# cell_fuses.net
KiCad netlist of a schematic drawn in Altium Designer
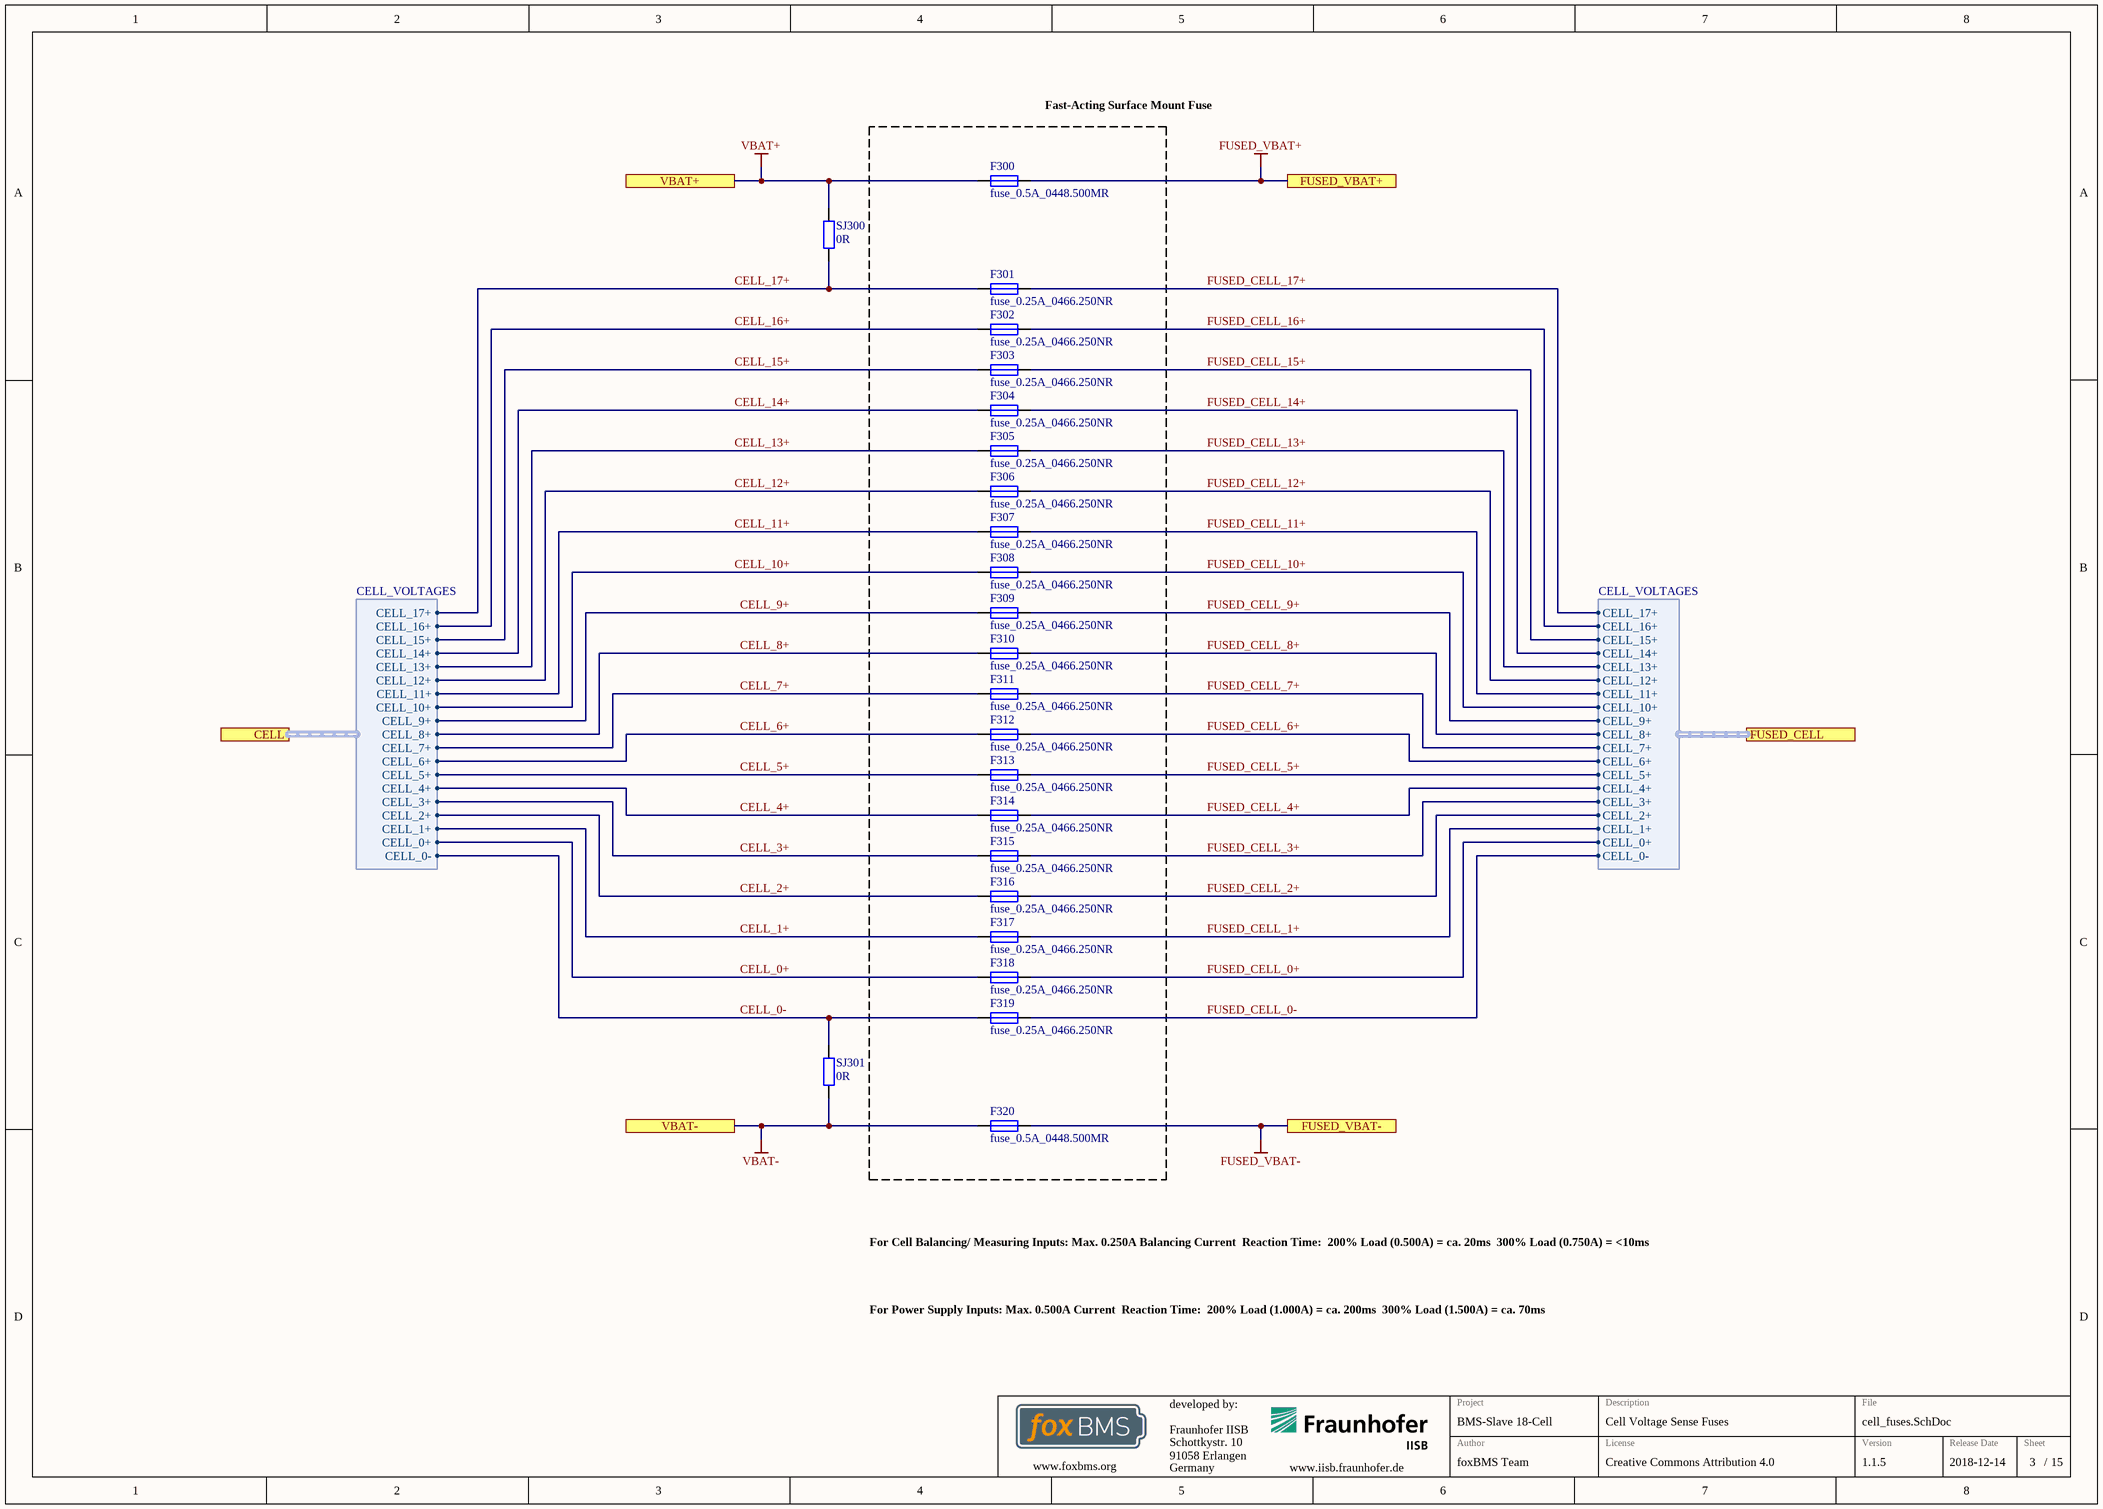
[diagram p0: cell_fuses.SchDoc]

(export (version "E")
  (design (tool "Eeschema 10.0.6"))
  (components
    (comp (ref "F300")
      (value "fuse_0.5A_0448.500MR")
      (footprint "LITTLEFUSE_448")
      (description "Fuse, Surface Mount, NANO2 Series, 500 mA, 125 VAC, 32 VDC, Very Fast Acting, SMD")
      (fields (field (name "MANUFACTURER") "Littlefuse"))
      (libsource (lib "OE750") (part "R_Fuse"))
    )
    (comp (ref "F301")
      (value "fuse_0.25A_0466.250NR")
      (footprint "LITTLEFUSE_466")
      (description "Fuse, Surface Mount, 466 Series, 250 mA, 125 VAC, 125 VDC, Very Fast Acting, 1206")
      (fields (field (name "MANUFACTURER") "Littlefuse"))
      (libsource (lib "OE750") (part "R_Fuse"))
    )
    (comp (ref "F302")
      (value "fuse_0.25A_0466.250NR")
      (footprint "LITTLEFUSE_466")
      (description "Fuse, Surface Mount, 466 Series, 250 mA, 125 VAC, 125 VDC, Very Fast Acting, 1206")
      (fields (field (name "MANUFACTURER") "Littlefuse"))
      (libsource (lib "OE750") (part "R_Fuse"))
    )
    (comp (ref "F303")
      (value "fuse_0.25A_0466.250NR")
      (footprint "LITTLEFUSE_466")
      (description "Fuse, Surface Mount, 466 Series, 250 mA, 125 VAC, 125 VDC, Very Fast Acting, 1206")
      (fields (field (name "MANUFACTURER") "Littlefuse"))
      (libsource (lib "OE750") (part "R_Fuse"))
    )
    (comp (ref "F304")
      (value "fuse_0.25A_0466.250NR")
      (footprint "LITTLEFUSE_466")
      (description "Fuse, Surface Mount, 466 Series, 250 mA, 125 VAC, 125 VDC, Very Fast Acting, 1206")
      (fields (field (name "MANUFACTURER") "Littlefuse"))
      (libsource (lib "OE750") (part "R_Fuse"))
    )
    (comp (ref "F305")
      (value "fuse_0.25A_0466.250NR")
      (footprint "LITTLEFUSE_466")
      (description "Fuse, Surface Mount, 466 Series, 250 mA, 125 VAC, 125 VDC, Very Fast Acting, 1206")
      (fields (field (name "MANUFACTURER") "Littlefuse"))
      (libsource (lib "OE750") (part "R_Fuse"))
    )
    (comp (ref "F306")
      (value "fuse_0.25A_0466.250NR")
      (footprint "LITTLEFUSE_466")
      (description "Fuse, Surface Mount, 466 Series, 250 mA, 125 VAC, 125 VDC, Very Fast Acting, 1206")
      (fields (field (name "MANUFACTURER") "Littlefuse"))
      (libsource (lib "OE750") (part "R_Fuse"))
    )
    (comp (ref "F307")
      (value "fuse_0.25A_0466.250NR")
      (footprint "LITTLEFUSE_466")
      (description "Fuse, Surface Mount, 466 Series, 250 mA, 125 VAC, 125 VDC, Very Fast Acting, 1206")
      (fields (field (name "MANUFACTURER") "Littlefuse"))
      (libsource (lib "OE750") (part "R_Fuse"))
    )
    (comp (ref "F308")
      (value "fuse_0.25A_0466.250NR")
      (footprint "LITTLEFUSE_466")
      (description "Fuse, Surface Mount, 466 Series, 250 mA, 125 VAC, 125 VDC, Very Fast Acting, 1206")
      (fields (field (name "MANUFACTURER") "Littlefuse"))
      (libsource (lib "OE750") (part "R_Fuse"))
    )
    (comp (ref "F309")
      (value "fuse_0.25A_0466.250NR")
      (footprint "LITTLEFUSE_466")
      (description "Fuse, Surface Mount, 466 Series, 250 mA, 125 VAC, 125 VDC, Very Fast Acting, 1206")
      (fields (field (name "MANUFACTURER") "Littlefuse"))
      (libsource (lib "OE750") (part "R_Fuse"))
    )
    (comp (ref "F310")
      (value "fuse_0.25A_0466.250NR")
      (footprint "LITTLEFUSE_466")
      (description "Fuse, Surface Mount, 466 Series, 250 mA, 125 VAC, 125 VDC, Very Fast Acting, 1206")
      (fields (field (name "MANUFACTURER") "Littlefuse"))
      (libsource (lib "OE750") (part "R_Fuse"))
    )
    (comp (ref "F311")
      (value "fuse_0.25A_0466.250NR")
      (footprint "LITTLEFUSE_466")
      (description "Fuse, Surface Mount, 466 Series, 250 mA, 125 VAC, 125 VDC, Very Fast Acting, 1206")
      (fields (field (name "MANUFACTURER") "Littlefuse"))
      (libsource (lib "OE750") (part "R_Fuse"))
    )
    (comp (ref "F312")
      (value "fuse_0.25A_0466.250NR")
      (footprint "LITTLEFUSE_466")
      (description "Fuse, Surface Mount, 466 Series, 250 mA, 125 VAC, 125 VDC, Very Fast Acting, 1206")
      (fields (field (name "MANUFACTURER") "Littlefuse"))
      (libsource (lib "OE750") (part "R_Fuse"))
    )
    (comp (ref "F313")
      (value "fuse_0.25A_0466.250NR")
      (footprint "LITTLEFUSE_466")
      (description "Fuse, Surface Mount, 466 Series, 250 mA, 125 VAC, 125 VDC, Very Fast Acting, 1206")
      (fields (field (name "MANUFACTURER") "Littlefuse"))
      (libsource (lib "OE750") (part "R_Fuse"))
    )
    (comp (ref "F314")
      (value "fuse_0.25A_0466.250NR")
      (footprint "LITTLEFUSE_466")
      (description "Fuse, Surface Mount, 466 Series, 250 mA, 125 VAC, 125 VDC, Very Fast Acting, 1206")
      (fields (field (name "MANUFACTURER") "Littlefuse"))
      (libsource (lib "OE750") (part "R_Fuse"))
    )
    (comp (ref "F315")
      (value "fuse_0.25A_0466.250NR")
      (footprint "LITTLEFUSE_466")
      (description "Fuse, Surface Mount, 466 Series, 250 mA, 125 VAC, 125 VDC, Very Fast Acting, 1206")
      (fields (field (name "MANUFACTURER") "Littlefuse"))
      (libsource (lib "OE750") (part "R_Fuse"))
    )
    (comp (ref "F316")
      (value "fuse_0.25A_0466.250NR")
      (footprint "LITTLEFUSE_466")
      (description "Fuse, Surface Mount, 466 Series, 250 mA, 125 VAC, 125 VDC, Very Fast Acting, 1206")
      (fields (field (name "MANUFACTURER") "Littlefuse"))
      (libsource (lib "OE750") (part "R_Fuse"))
    )
    (comp (ref "F317")
      (value "fuse_0.25A_0466.250NR")
      (footprint "LITTLEFUSE_466")
      (description "Fuse, Surface Mount, 466 Series, 250 mA, 125 VAC, 125 VDC, Very Fast Acting, 1206")
      (fields (field (name "MANUFACTURER") "Littlefuse"))
      (libsource (lib "OE750") (part "R_Fuse"))
    )
    (comp (ref "F318")
      (value "fuse_0.25A_0466.250NR")
      (footprint "LITTLEFUSE_466")
      (description "Fuse, Surface Mount, 466 Series, 250 mA, 125 VAC, 125 VDC, Very Fast Acting, 1206")
      (fields (field (name "MANUFACTURER") "Littlefuse"))
      (libsource (lib "OE750") (part "R_Fuse"))
    )
    (comp (ref "F319")
      (value "fuse_0.25A_0466.250NR")
      (footprint "LITTLEFUSE_466")
      (description "Fuse, Surface Mount, 466 Series, 250 mA, 125 VAC, 125 VDC, Very Fast Acting, 1206")
      (fields (field (name "MANUFACTURER") "Littlefuse"))
      (libsource (lib "OE750") (part "R_Fuse"))
    )
    (comp (ref "F320")
      (value "fuse_0.5A_0448.500MR")
      (footprint "LITTLEFUSE_448")
      (description "Fuse, Surface Mount, NANO2 Series, 500 mA, 125 VAC, 32 VDC, Very Fast Acting, SMD")
      (fields (field (name "MANUFACTURER") "Littlefuse"))
      (libsource (lib "OE750") (part "R_Fuse"))
    )
    (comp (ref "SJ300")
      (value "0R")
      (footprint "RESC1608X05N")
      (description "SMD Resistor 0R 0603")
      (fields (field (name "PART NUMBER") "gen_R_0R_0603") (field (name "POWER") "0.1W"))
      (libsource (lib "OE750") (part "R"))
    )
    (comp (ref "SJ301")
      (value "0R")
      (footprint "RESC1608X05N")
      (description "SMD Resistor 0R 0603")
      (fields (field (name "PART NUMBER") "gen_R_0R_0603") (field (name "POWER") "0.1W"))
      (libsource (lib "OE750") (part "R"))
    )
  )
  (nets
    (net (code "2") (name "/CELL_0+") (class "Default")
      (node (ref "F318") (pin "1") (pinfunction "1_1") (pintype "passive"))
    )
    (net (code "3") (name "/CELL_0-") (class "Default")
      (node (ref "F319") (pin "1") (pinfunction "1_1") (pintype "passive"))
      (node (ref "SJ301") (pin "1") (pinfunction "1_1") (pintype "passive"))
    )
    (net (code "4") (name "/CELL_1+") (class "Default")
      (node (ref "F317") (pin "1") (pinfunction "1_1") (pintype "passive"))
    )
    (net (code "5") (name "/CELL_2+") (class "Default")
      (node (ref "F316") (pin "1") (pinfunction "1_1") (pintype "passive"))
    )
    (net (code "6") (name "/CELL_3+") (class "Default")
      (node (ref "F315") (pin "1") (pinfunction "1_1") (pintype "passive"))
    )
    (net (code "7") (name "/CELL_4+") (class "Default")
      (node (ref "F314") (pin "1") (pinfunction "1_1") (pintype "passive"))
    )
    (net (code "8") (name "/CELL_5+") (class "Default")
      (node (ref "F313") (pin "1") (pinfunction "1_1") (pintype "passive"))
    )
    (net (code "9") (name "/CELL_6+") (class "Default")
      (node (ref "F312") (pin "1") (pinfunction "1_1") (pintype "passive"))
    )
    (net (code "10") (name "/CELL_7+") (class "Default")
      (node (ref "F311") (pin "1") (pinfunction "1_1") (pintype "passive"))
    )
    (net (code "11") (name "/CELL_8+") (class "Default")
      (node (ref "F310") (pin "1") (pinfunction "1_1") (pintype "passive"))
    )
    (net (code "12") (name "/CELL_9+") (class "Default")
      (node (ref "F309") (pin "1") (pinfunction "1_1") (pintype "passive"))
    )
    (net (code "13") (name "/CELL_10+") (class "Default")
      (node (ref "F308") (pin "1") (pinfunction "1_1") (pintype "passive"))
    )
    (net (code "14") (name "/CELL_11+") (class "Default")
      (node (ref "F307") (pin "1") (pinfunction "1_1") (pintype "passive"))
    )
    (net (code "15") (name "/CELL_12+") (class "Default")
      (node (ref "F306") (pin "1") (pinfunction "1_1") (pintype "passive"))
    )
    (net (code "16") (name "/CELL_13+") (class "Default")
      (node (ref "F305") (pin "1") (pinfunction "1_1") (pintype "passive"))
    )
    (net (code "17") (name "/CELL_14+") (class "Default")
      (node (ref "F304") (pin "1") (pinfunction "1_1") (pintype "passive"))
    )
    (net (code "18") (name "/CELL_15+") (class "Default")
      (node (ref "F303") (pin "1") (pinfunction "1_1") (pintype "passive"))
    )
    (net (code "19") (name "/CELL_16+") (class "Default")
      (node (ref "F302") (pin "1") (pinfunction "1_1") (pintype "passive"))
    )
    (net (code "20") (name "/CELL_17+") (class "Default")
      (node (ref "F301") (pin "1") (pinfunction "1_1") (pintype "passive"))
      (node (ref "SJ300") (pin "2") (pinfunction "2_2") (pintype "passive"))
    )
    (net (code "21") (name "/FUSED_CELL_0+") (class "Default")
      (node (ref "F318") (pin "2") (pinfunction "2_2") (pintype "passive"))
    )
    (net (code "22") (name "/FUSED_CELL_0-") (class "Default")
      (node (ref "F319") (pin "2") (pinfunction "2_2") (pintype "passive"))
    )
    (net (code "23") (name "/FUSED_CELL_1+") (class "Default")
      (node (ref "F317") (pin "2") (pinfunction "2_2") (pintype "passive"))
    )
    (net (code "24") (name "/FUSED_CELL_2+") (class "Default")
      (node (ref "F316") (pin "2") (pinfunction "2_2") (pintype "passive"))
    )
    (net (code "25") (name "/FUSED_CELL_3+") (class "Default")
      (node (ref "F315") (pin "2") (pinfunction "2_2") (pintype "passive"))
    )
    (net (code "26") (name "/FUSED_CELL_4+") (class "Default")
      (node (ref "F314") (pin "2") (pinfunction "2_2") (pintype "passive"))
    )
    (net (code "27") (name "/FUSED_CELL_5+") (class "Default")
      (node (ref "F313") (pin "2") (pinfunction "2_2") (pintype "passive"))
    )
    (net (code "28") (name "/FUSED_CELL_6+") (class "Default")
      (node (ref "F312") (pin "2") (pinfunction "2_2") (pintype "passive"))
    )
    (net (code "29") (name "/FUSED_CELL_7+") (class "Default")
      (node (ref "F311") (pin "2") (pinfunction "2_2") (pintype "passive"))
    )
    (net (code "30") (name "/FUSED_CELL_8+") (class "Default")
      (node (ref "F310") (pin "2") (pinfunction "2_2") (pintype "passive"))
    )
    (net (code "31") (name "/FUSED_CELL_9+") (class "Default")
      (node (ref "F309") (pin "2") (pinfunction "2_2") (pintype "passive"))
    )
    (net (code "32") (name "/FUSED_CELL_10+") (class "Default")
      (node (ref "F308") (pin "2") (pinfunction "2_2") (pintype "passive"))
    )
    (net (code "33") (name "/FUSED_CELL_11+") (class "Default")
      (node (ref "F307") (pin "2") (pinfunction "2_2") (pintype "passive"))
    )
    (net (code "34") (name "/FUSED_CELL_12+") (class "Default")
      (node (ref "F306") (pin "2") (pinfunction "2_2") (pintype "passive"))
    )
    (net (code "35") (name "/FUSED_CELL_13+") (class "Default")
      (node (ref "F305") (pin "2") (pinfunction "2_2") (pintype "passive"))
    )
    (net (code "36") (name "/FUSED_CELL_14+") (class "Default")
      (node (ref "F304") (pin "2") (pinfunction "2_2") (pintype "passive"))
    )
    (net (code "37") (name "/FUSED_CELL_15+") (class "Default")
      (node (ref "F303") (pin "2") (pinfunction "2_2") (pintype "passive"))
    )
    (net (code "38") (name "/FUSED_CELL_16+") (class "Default")
      (node (ref "F302") (pin "2") (pinfunction "2_2") (pintype "passive"))
    )
    (net (code "39") (name "/FUSED_CELL_17+") (class "Default")
      (node (ref "F301") (pin "2") (pinfunction "2_2") (pintype "passive"))
    )
    (net (code "41") (name "FUSED_VBAT+") (class "Default")
      (node (ref "F300") (pin "2") (pinfunction "2_2") (pintype "passive"))
    )
    (net (code "42") (name "FUSED_VBAT-") (class "Default")
      (node (ref "F320") (pin "2") (pinfunction "2_2") (pintype "passive"))
    )
    (net (code "43") (name "VBAT+") (class "Default")
      (node (ref "F300") (pin "1") (pinfunction "1_1") (pintype "passive"))
      (node (ref "SJ300") (pin "1") (pinfunction "1_1") (pintype "passive"))
    )
    (net (code "44") (name "VBAT-") (class "Default")
      (node (ref "F320") (pin "1") (pinfunction "1_1") (pintype "passive"))
      (node (ref "SJ301") (pin "2") (pinfunction "2_2") (pintype "passive"))
    )
  )
)
